# main.net
KiCad netlist of a schematic drawn in Altium Designer
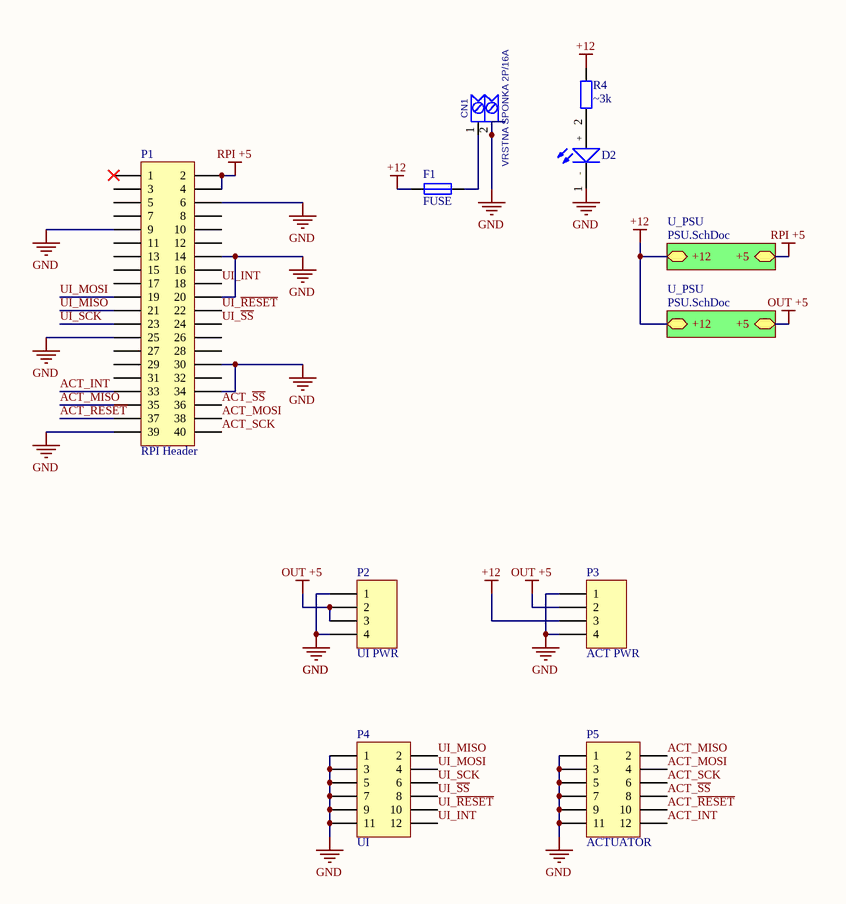
[diagram p0: main.SchDoc]

(export (version "E")
  (design (tool "Eeschema 10.0.6"))
  (components
    (comp (ref "CN1")
      (value "VRSTNA SPONKA 2P/16A")
      (footprint "VRSTNA SPONKA 2P/16A")
      (libsource (lib "Kon_Tipk") (part "VRSTNA SPONKA 2P/16A"))
    )
    (comp (ref "D2") (value "LED") (footprint "LED1608_0603I_L") (libsource (lib "General") (part "LED")))
    (comp (ref "F1") (value "FUSE") (footprint "R1005_0402i_M") (libsource (lib "General") (part "FUSE")))
    (comp (ref "P1")
      (value "RPI Header")
      (footprint "HDR2X20")
      (description "Header, 20-Pin, Dual row")
      (fields (field (name "PUBLISHER") "Altium Limited"))
      (libsource (lib "Miscellaneous Connectors") (part "Header 20X2"))
    )
    (comp (ref "P2")
      (value "UI PWR")
      (footprint "HDR1X4")
      (description "Header, 4-Pin")
      (fields (field (name "PUBLISHER") "Altium Limited"))
      (libsource (lib "Miscellaneous Connectors") (part "Header 4"))
    )
    (comp (ref "P3")
      (value "ACT PWR")
      (footprint "HDR1X4")
      (description "Header, 4-Pin")
      (fields (field (name "PUBLISHER") "Altium Limited"))
      (libsource (lib "Miscellaneous Connectors") (part "Header 4"))
    )
    (comp (ref "P4")
      (value "UI")
      (footprint "1.27mm headet tht")
      (description "Header, 6-Pin, Dual row")
      (fields (field (name "PUBLISHER") "Altium Limited"))
      (libsource (lib "Miscellaneous Connectors") (part "Header 6X2"))
    )
    (comp (ref "P5")
      (value "ACTUATOR")
      (footprint "1.27mm headet tht")
      (description "Header, 6-Pin, Dual row")
      (fields (field (name "PUBLISHER") "Altium Limited"))
      (libsource (lib "Miscellaneous Connectors") (part "Header 6X2"))
    )
    (comp (ref "R4")
      (value "~3k")
      (footprint "R1005_0402i_L")
      (description "R")
      (libsource (lib "General") (part "R"))
    )
  )
  (nets
    (net (code "1") (name "+12") (class "Default")
      (node (ref "F1") (pin "1") (pinfunction "1_1") (pintype "passive"))
      (node (ref "P3") (pin "3") (pinfunction "3_3") (pintype "passive"))
      (node (ref "R4") (pin "1") (pintype "passive"))
    )
    (net (code "2") (name "/ACT_INT") (class "Default")
      (node (ref "P1") (pin "33") (pinfunction "33_33") (pintype "passive"))
      (node (ref "P5") (pin "12") (pinfunction "12_12") (pintype "passive"))
    )
    (net (code "3") (name "/ACT_MISO") (class "Default")
      (node (ref "P1") (pin "35") (pinfunction "35_35") (pintype "passive"))
      (node (ref "P5") (pin "2") (pinfunction "2_2") (pintype "passive"))
    )
    (net (code "4") (name "/ACT_MOSI") (class "Default")
      (node (ref "P1") (pin "38") (pinfunction "38_38") (pintype "passive"))
      (node (ref "P5") (pin "4") (pinfunction "4_4") (pintype "passive"))
    )
    (net (code "5") (name "/ACT_SCK") (class "Default")
      (node (ref "P1") (pin "40") (pinfunction "40_40") (pintype "passive"))
      (node (ref "P5") (pin "6") (pinfunction "6_6") (pintype "passive"))
    )
    (net (code "6") (name "/ACT_~{RESET}") (class "Default")
      (node (ref "P1") (pin "37") (pinfunction "37_37") (pintype "passive"))
      (node (ref "P5") (pin "10") (pinfunction "10_10") (pintype "passive"))
    )
    (net (code "7") (name "/ACT_~{SS}") (class "Default")
      (node (ref "P1") (pin "36") (pinfunction "36_36") (pintype "passive"))
      (node (ref "P5") (pin "8") (pinfunction "8_8") (pintype "passive"))
    )
    (net (code "8") (name "/UI_INT") (class "Default")
      (node (ref "P1") (pin "18") (pinfunction "18_18") (pintype "passive"))
      (node (ref "P4") (pin "12") (pinfunction "12_12") (pintype "passive"))
    )
    (net (code "9") (name "/UI_MISO") (class "Default")
      (node (ref "P1") (pin "21") (pinfunction "21_21") (pintype "passive"))
      (node (ref "P4") (pin "2") (pinfunction "2_2") (pintype "passive"))
    )
    (net (code "10") (name "/UI_MOSI") (class "Default")
      (node (ref "P1") (pin "19") (pinfunction "19_19") (pintype "passive"))
      (node (ref "P4") (pin "4") (pinfunction "4_4") (pintype "passive"))
    )
    (net (code "11") (name "/UI_SCK") (class "Default")
      (node (ref "P1") (pin "23") (pinfunction "23_23") (pintype "passive"))
      (node (ref "P4") (pin "6") (pinfunction "6_6") (pintype "passive"))
    )
    (net (code "12") (name "/UI_~{RESET}") (class "Default")
      (node (ref "P1") (pin "22") (pinfunction "22_22") (pintype "passive"))
      (node (ref "P4") (pin "10") (pinfunction "10_10") (pintype "passive"))
    )
    (net (code "13") (name "/UI_~{SS}") (class "Default")
      (node (ref "P1") (pin "24") (pinfunction "24_24") (pintype "passive"))
      (node (ref "P4") (pin "8") (pinfunction "8_8") (pintype "passive"))
    )
    (net (code "14") (name "GND") (class "Default")
      (node (ref "CN1") (pin "2") (pintype "passive"))
      (node (ref "D2") (pin "1") (pinfunction "-_1") (pintype "passive"))
      (node (ref "P1") (pin "14") (pinfunction "14_14") (pintype "passive"))
      (node (ref "P1") (pin "20") (pinfunction "20_20") (pintype "passive"))
      (node (ref "P1") (pin "25") (pinfunction "25_25") (pintype "passive"))
      (node (ref "P1") (pin "30") (pinfunction "30_30") (pintype "passive"))
      (node (ref "P1") (pin "34") (pinfunction "34_34") (pintype "passive"))
      (node (ref "P1") (pin "39") (pinfunction "39_39") (pintype "passive"))
      (node (ref "P1") (pin "6") (pinfunction "6_6") (pintype "passive"))
      (node (ref "P1") (pin "9") (pinfunction "9_9") (pintype "passive"))
      (node (ref "P2") (pin "1") (pinfunction "1_1") (pintype "passive"))
      (node (ref "P2") (pin "4") (pinfunction "4_4") (pintype "passive"))
      (node (ref "P3") (pin "1") (pinfunction "1_1") (pintype "passive"))
      (node (ref "P3") (pin "4") (pinfunction "4_4") (pintype "passive"))
      (node (ref "P4") (pin "1") (pinfunction "1_1") (pintype "passive"))
      (node (ref "P4") (pin "11") (pinfunction "11_11") (pintype "passive"))
      (node (ref "P4") (pin "3") (pinfunction "3_3") (pintype "passive"))
      (node (ref "P4") (pin "5") (pinfunction "5_5") (pintype "passive"))
      (node (ref "P4") (pin "7") (pinfunction "7_7") (pintype "passive"))
      (node (ref "P4") (pin "9") (pinfunction "9_9") (pintype "passive"))
      (node (ref "P5") (pin "1") (pinfunction "1_1") (pintype "passive"))
      (node (ref "P5") (pin "11") (pinfunction "11_11") (pintype "passive"))
      (node (ref "P5") (pin "3") (pinfunction "3_3") (pintype "passive"))
      (node (ref "P5") (pin "5") (pinfunction "5_5") (pintype "passive"))
      (node (ref "P5") (pin "7") (pinfunction "7_7") (pintype "passive"))
      (node (ref "P5") (pin "9") (pinfunction "9_9") (pintype "passive"))
    )
    (net (code "15") (name "Net-(CN1-Pad1)") (class "Default")
      (node (ref "CN1") (pin "1") (pintype "passive"))
      (node (ref "F1") (pin "2") (pinfunction "2_2") (pintype "passive"))
    )
    (net (code "16") (name "Net-(D2-+)") (class "Default")
      (node (ref "D2") (pin "2") (pinfunction "+_2") (pintype "passive"))
      (node (ref "R4") (pin "2") (pintype "passive"))
    )
    (net (code "17") (name "OUT +5") (class "Default")
      (node (ref "P2") (pin "2") (pinfunction "2_2") (pintype "passive"))
      (node (ref "P2") (pin "3") (pinfunction "3_3") (pintype "passive"))
      (node (ref "P3") (pin "2") (pinfunction "2_2") (pintype "passive"))
    )
    (net (code "18") (name "RPI +5") (class "Default")
      (node (ref "P1") (pin "2") (pinfunction "2_2") (pintype "passive"))
      (node (ref "P1") (pin "4") (pinfunction "4_4") (pintype "passive"))
    )
    (net (code "19") (name "unconnected-(P1-Pad1)") (class "Default")
      (node (ref "P1") (pin "1") (pinfunction "1_1") (pintype "passive+no_connect"))
    )
    (net (code "20") (name "unconnected-(P1-Pad3)") (class "Default")
      (node (ref "P1") (pin "3") (pinfunction "3_3") (pintype "passive"))
    )
    (net (code "21") (name "unconnected-(P1-Pad5)") (class "Default")
      (node (ref "P1") (pin "5") (pinfunction "5_5") (pintype "passive"))
    )
    (net (code "22") (name "unconnected-(P1-Pad7)") (class "Default")
      (node (ref "P1") (pin "7") (pinfunction "7_7") (pintype "passive"))
    )
    (net (code "23") (name "unconnected-(P1-Pad8)") (class "Default")
      (node (ref "P1") (pin "8") (pinfunction "8_8") (pintype "passive"))
    )
    (net (code "24") (name "unconnected-(P1-Pad10)") (class "Default")
      (node (ref "P1") (pin "10") (pinfunction "10_10") (pintype "passive"))
    )
    (net (code "25") (name "unconnected-(P1-Pad11)") (class "Default")
      (node (ref "P1") (pin "11") (pinfunction "11_11") (pintype "passive"))
    )
    (net (code "26") (name "unconnected-(P1-Pad12)") (class "Default")
      (node (ref "P1") (pin "12") (pinfunction "12_12") (pintype "passive"))
    )
    (net (code "27") (name "unconnected-(P1-Pad13)") (class "Default")
      (node (ref "P1") (pin "13") (pinfunction "13_13") (pintype "passive"))
    )
    (net (code "28") (name "unconnected-(P1-Pad15)") (class "Default")
      (node (ref "P1") (pin "15") (pinfunction "15_15") (pintype "passive"))
    )
    (net (code "29") (name "unconnected-(P1-Pad16)") (class "Default")
      (node (ref "P1") (pin "16") (pinfunction "16_16") (pintype "passive"))
    )
    (net (code "30") (name "unconnected-(P1-Pad17)") (class "Default")
      (node (ref "P1") (pin "17") (pinfunction "17_17") (pintype "passive"))
    )
    (net (code "31") (name "unconnected-(P1-Pad26)") (class "Default")
      (node (ref "P1") (pin "26") (pinfunction "26_26") (pintype "passive"))
    )
    (net (code "32") (name "unconnected-(P1-Pad27)") (class "Default")
      (node (ref "P1") (pin "27") (pinfunction "27_27") (pintype "passive"))
    )
    (net (code "33") (name "unconnected-(P1-Pad28)") (class "Default")
      (node (ref "P1") (pin "28") (pinfunction "28_28") (pintype "passive"))
    )
    (net (code "34") (name "unconnected-(P1-Pad29)") (class "Default")
      (node (ref "P1") (pin "29") (pinfunction "29_29") (pintype "passive"))
    )
    (net (code "35") (name "unconnected-(P1-Pad31)") (class "Default")
      (node (ref "P1") (pin "31") (pinfunction "31_31") (pintype "passive"))
    )
    (net (code "36") (name "unconnected-(P1-Pad32)") (class "Default")
      (node (ref "P1") (pin "32") (pinfunction "32_32") (pintype "passive"))
    )
  )
)
